# SG1000_-_SMS_PP.net
KiCad netlist of a schematic drawn in EAGLE
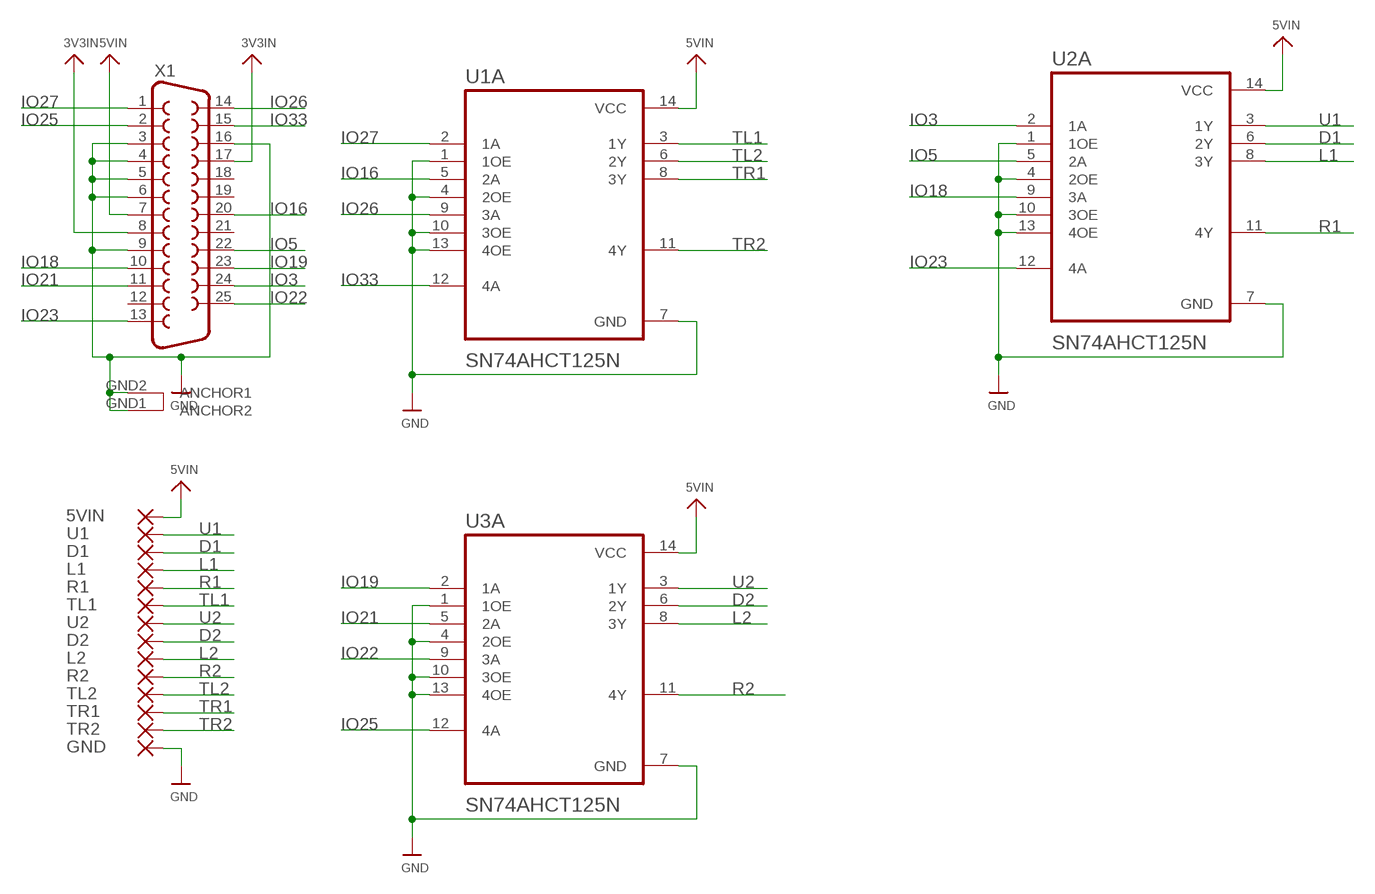
[diagram p0: schematic, sheet 1]

(export (version "E")
  (design (tool "Eeschema 10.0.6"))
  (components
    (comp (ref "5VIN")
      (value "SMD5")
      (footprint "eagle-import:SMD2,54-5,08")
      (libsource (lib "eagle-import") (part "SMD5"))
    )
    (comp (ref "D1")
      (value "SMD5")
      (footprint "eagle-import:SMD2,54-5,08")
      (libsource (lib "eagle-import") (part "SMD5"))
    )
    (comp (ref "D2")
      (value "SMD5")
      (footprint "eagle-import:SMD2,54-5,08")
      (libsource (lib "eagle-import") (part "SMD5"))
    )
    (comp (ref "GND")
      (value "SMD5")
      (footprint "eagle-import:SMD2,54-5,08")
      (libsource (lib "eagle-import") (part "SMD5"))
    )
    (comp (ref "L1")
      (value "SMD5")
      (footprint "eagle-import:SMD2,54-5,08")
      (libsource (lib "eagle-import") (part "SMD5"))
    )
    (comp (ref "L2")
      (value "SMD5")
      (footprint "eagle-import:SMD2,54-5,08")
      (libsource (lib "eagle-import") (part "SMD5"))
    )
    (comp (ref "R1")
      (value "SMD5")
      (footprint "eagle-import:SMD2,54-5,08")
      (libsource (lib "eagle-import") (part "SMD5"))
    )
    (comp (ref "R2")
      (value "SMD5")
      (footprint "eagle-import:SMD2,54-5,08")
      (libsource (lib "eagle-import") (part "SMD5"))
    )
    (comp (ref "TL1")
      (value "SMD5")
      (footprint "eagle-import:SMD2,54-5,08")
      (libsource (lib "eagle-import") (part "SMD5"))
    )
    (comp (ref "TL2")
      (value "SMD5")
      (footprint "eagle-import:SMD2,54-5,08")
      (libsource (lib "eagle-import") (part "SMD5"))
    )
    (comp (ref "TR1")
      (value "SMD5")
      (footprint "eagle-import:SMD2,54-5,08")
      (libsource (lib "eagle-import") (part "SMD5"))
    )
    (comp (ref "TR2")
      (value "SMD5")
      (footprint "eagle-import:SMD2,54-5,08")
      (libsource (lib "eagle-import") (part "SMD5"))
    )
    (comp (ref "U1")
      (value "SMD5")
      (footprint "eagle-import:SMD2,54-5,08")
      (libsource (lib "eagle-import") (part "SMD5"))
    )
    (comp (ref "U1A")
      (value "SN74AHCT125N")
      (footprint "eagle-import:DIP794W45P254L1969H508Q14")
      (fields (field (name "MF") "Texas Instruments"))
      (libsource (lib "eagle-import") (part "SN74AHCT125N"))
    )
    (comp (ref "U2")
      (value "SMD5")
      (footprint "eagle-import:SMD2,54-5,08")
      (libsource (lib "eagle-import") (part "SMD5"))
    )
    (comp (ref "U2A")
      (value "SN74AHCT125N")
      (footprint "eagle-import:DIP794W45P254L1969H508Q14")
      (fields (field (name "MF") "Texas Instruments"))
      (libsource (lib "eagle-import") (part "SN74AHCT125N"))
    )
    (comp (ref "U3A")
      (value "SN74AHCT125N")
      (footprint "eagle-import:DIP794W45P254L1969H508Q14")
      (fields (field (name "MF") "Texas Instruments"))
      (libsource (lib "eagle-import") (part "SN74AHCT125N"))
    )
    (comp (ref "X1")
      (value "DB25_FEMALEHP")
      (footprint "eagle-import:F25HP")
      (libsource (lib "eagle-import") (part "DB25_FEMALEHP"))
    )
  )
  (nets
    (net (code "1") (name "/D1") (class "Default")
      (node (ref "D1") (pin "1") (pinfunction "P_1") (pintype "passive"))
      (node (ref "U2A") (pin "6") (pinfunction "2Y_6") (pintype "output"))
    )
    (net (code "2") (name "/D2") (class "Default")
      (node (ref "D2") (pin "1") (pinfunction "P_1") (pintype "passive"))
      (node (ref "U3A") (pin "6") (pinfunction "2Y_6") (pintype "output"))
    )
    (net (code "3") (name "/IO3") (class "Default")
      (node (ref "U2A") (pin "2") (pinfunction "1A_2") (pintype "input"))
      (node (ref "X1") (pin "24") (pinfunction "24_24") (pintype "passive"))
    )
    (net (code "4") (name "/IO5") (class "Default")
      (node (ref "U2A") (pin "5") (pinfunction "2A_5") (pintype "input"))
      (node (ref "X1") (pin "22") (pinfunction "22_22") (pintype "passive"))
    )
    (net (code "5") (name "/IO16") (class "Default")
      (node (ref "U1A") (pin "5") (pinfunction "2A_5") (pintype "input"))
      (node (ref "X1") (pin "20") (pinfunction "20_20") (pintype "passive"))
    )
    (net (code "6") (name "/IO18") (class "Default")
      (node (ref "U2A") (pin "9") (pinfunction "3A_9") (pintype "input"))
      (node (ref "X1") (pin "10") (pinfunction "10_10") (pintype "passive"))
    )
    (net (code "7") (name "/IO19") (class "Default")
      (node (ref "U3A") (pin "2") (pinfunction "1A_2") (pintype "input"))
      (node (ref "X1") (pin "23") (pinfunction "23_23") (pintype "passive"))
    )
    (net (code "8") (name "/IO21") (class "Default")
      (node (ref "U3A") (pin "5") (pinfunction "2A_5") (pintype "input"))
      (node (ref "X1") (pin "11") (pinfunction "11_11") (pintype "passive"))
    )
    (net (code "9") (name "/IO22") (class "Default")
      (node (ref "U3A") (pin "9") (pinfunction "3A_9") (pintype "input"))
      (node (ref "X1") (pin "25") (pinfunction "25_25") (pintype "passive"))
    )
    (net (code "10") (name "/IO23") (class "Default")
      (node (ref "U2A") (pin "12") (pinfunction "4A_12") (pintype "bidirectional"))
      (node (ref "X1") (pin "13") (pinfunction "13_13") (pintype "passive"))
    )
    (net (code "11") (name "/IO25") (class "Default")
      (node (ref "U3A") (pin "12") (pinfunction "4A_12") (pintype "bidirectional"))
      (node (ref "X1") (pin "2") (pinfunction "2_2") (pintype "passive"))
    )
    (net (code "12") (name "/IO26") (class "Default")
      (node (ref "U1A") (pin "9") (pinfunction "3A_9") (pintype "input"))
      (node (ref "X1") (pin "14") (pinfunction "14_14") (pintype "passive"))
    )
    (net (code "13") (name "/IO27") (class "Default")
      (node (ref "U1A") (pin "2") (pinfunction "1A_2") (pintype "input"))
      (node (ref "X1") (pin "1") (pinfunction "1_1") (pintype "passive"))
    )
    (net (code "14") (name "/IO33") (class "Default")
      (node (ref "U1A") (pin "12") (pinfunction "4A_12") (pintype "bidirectional"))
      (node (ref "X1") (pin "15") (pinfunction "15_15") (pintype "passive"))
    )
    (net (code "15") (name "/L1") (class "Default")
      (node (ref "L1") (pin "1") (pinfunction "P_1") (pintype "passive"))
      (node (ref "U2A") (pin "8") (pinfunction "3Y_8") (pintype "output"))
    )
    (net (code "16") (name "/L2") (class "Default")
      (node (ref "L2") (pin "1") (pinfunction "P_1") (pintype "passive"))
      (node (ref "U3A") (pin "8") (pinfunction "3Y_8") (pintype "output"))
    )
    (net (code "17") (name "/R1") (class "Default")
      (node (ref "R1") (pin "1") (pinfunction "P_1") (pintype "passive"))
      (node (ref "U2A") (pin "11") (pinfunction "4Y_11") (pintype "output"))
    )
    (net (code "18") (name "/R2") (class "Default")
      (node (ref "R2") (pin "1") (pinfunction "P_1") (pintype "passive"))
      (node (ref "U3A") (pin "11") (pinfunction "4Y_11") (pintype "output"))
    )
    (net (code "19") (name "/TL1") (class "Default")
      (node (ref "TL1") (pin "1") (pinfunction "P_1") (pintype "passive"))
      (node (ref "U1A") (pin "3") (pinfunction "1Y_3") (pintype "output"))
    )
    (net (code "20") (name "/TL2") (class "Default")
      (node (ref "TL2") (pin "1") (pinfunction "P_1") (pintype "passive"))
      (node (ref "U1A") (pin "6") (pinfunction "2Y_6") (pintype "output"))
    )
    (net (code "21") (name "/TR1") (class "Default")
      (node (ref "TR1") (pin "1") (pinfunction "P_1") (pintype "passive"))
      (node (ref "U1A") (pin "8") (pinfunction "3Y_8") (pintype "output"))
    )
    (net (code "22") (name "/TR2") (class "Default")
      (node (ref "TR2") (pin "1") (pinfunction "P_1") (pintype "passive"))
      (node (ref "U1A") (pin "11") (pinfunction "4Y_11") (pintype "output"))
    )
    (net (code "23") (name "/U1") (class "Default")
      (node (ref "U1") (pin "1") (pinfunction "P_1") (pintype "passive"))
      (node (ref "U2A") (pin "3") (pinfunction "1Y_3") (pintype "output"))
    )
    (net (code "24") (name "/U2") (class "Default")
      (node (ref "U2") (pin "1") (pinfunction "P_1") (pintype "passive"))
      (node (ref "U3A") (pin "3") (pinfunction "1Y_3") (pintype "output"))
    )
    (net (code "25") (name "3V3IN") (class "Default")
      (node (ref "X1") (pin "17") (pinfunction "17_17") (pintype "passive"))
      (node (ref "X1") (pin "8") (pinfunction "8_8") (pintype "passive"))
    )
    (net (code "26") (name "5VIN") (class "Default")
      (node (ref "5VIN") (pin "1") (pinfunction "P_1") (pintype "passive"))
      (node (ref "U1A") (pin "14") (pinfunction "VCC_14") (pintype "power_in"))
      (node (ref "U2A") (pin "14") (pinfunction "VCC_14") (pintype "power_in"))
      (node (ref "U3A") (pin "14") (pinfunction "VCC_14") (pintype "power_in"))
      (node (ref "X1") (pin "7") (pinfunction "7_7") (pintype "passive"))
    )
    (net (code "27") (name "GND") (class "Default")
      (node (ref "GND") (pin "1") (pinfunction "P_1") (pintype "passive"))
      (node (ref "U1A") (pin "1") (pinfunction "1OE_1") (pintype "input"))
      (node (ref "U1A") (pin "10") (pinfunction "3OE_10") (pintype "input"))
      (node (ref "U1A") (pin "13") (pinfunction "4OE_13") (pintype "input"))
      (node (ref "U1A") (pin "4") (pinfunction "2OE_4") (pintype "input"))
      (node (ref "U1A") (pin "7") (pinfunction "GND_7") (pintype "power_in"))
      (node (ref "U2A") (pin "1") (pinfunction "1OE_1") (pintype "input"))
      (node (ref "U2A") (pin "10") (pinfunction "3OE_10") (pintype "input"))
      (node (ref "U2A") (pin "13") (pinfunction "4OE_13") (pintype "input"))
      (node (ref "U2A") (pin "4") (pinfunction "2OE_4") (pintype "input"))
      (node (ref "U2A") (pin "7") (pinfunction "GND_7") (pintype "power_in"))
      (node (ref "U3A") (pin "1") (pinfunction "1OE_1") (pintype "input"))
      (node (ref "U3A") (pin "10") (pinfunction "3OE_10") (pintype "input"))
      (node (ref "U3A") (pin "13") (pinfunction "4OE_13") (pintype "input"))
      (node (ref "U3A") (pin "4") (pinfunction "2OE_4") (pintype "input"))
      (node (ref "U3A") (pin "7") (pinfunction "GND_7") (pintype "power_in"))
      (node (ref "X1") (pin "16") (pinfunction "16_16") (pintype "passive"))
      (node (ref "X1") (pin "3") (pinfunction "3_3") (pintype "passive"))
      (node (ref "X1") (pin "4") (pinfunction "4_4") (pintype "passive"))
      (node (ref "X1") (pin "5") (pinfunction "5_5") (pintype "passive"))
      (node (ref "X1") (pin "6") (pinfunction "6_6") (pintype "passive"))
      (node (ref "X1") (pin "9") (pinfunction "9_9") (pintype "passive"))
      (node (ref "X1") (pin "GND1") (pinfunction "ANCHOR2_GND1") (pintype "bidirectional"))
      (node (ref "X1") (pin "GND2") (pinfunction "ANCHOR1_GND2") (pintype "bidirectional"))
    )
    (net (code "28") (name "unconnected-(X1-Pad12)") (class "Default")
      (node (ref "X1") (pin "12") (pinfunction "12_12") (pintype "passive"))
    )
    (net (code "29") (name "unconnected-(X1-Pad18)") (class "Default")
      (node (ref "X1") (pin "18") (pinfunction "18_18") (pintype "passive"))
    )
    (net (code "30") (name "unconnected-(X1-Pad19)") (class "Default")
      (node (ref "X1") (pin "19") (pinfunction "19_19") (pintype "passive"))
    )
    (net (code "31") (name "unconnected-(X1-Pad21)") (class "Default")
      (node (ref "X1") (pin "21") (pinfunction "21_21") (pintype "passive"))
    )
  )
)
